# charge_drv.net
KiCad netlist of a schematic drawn in Altium Designer
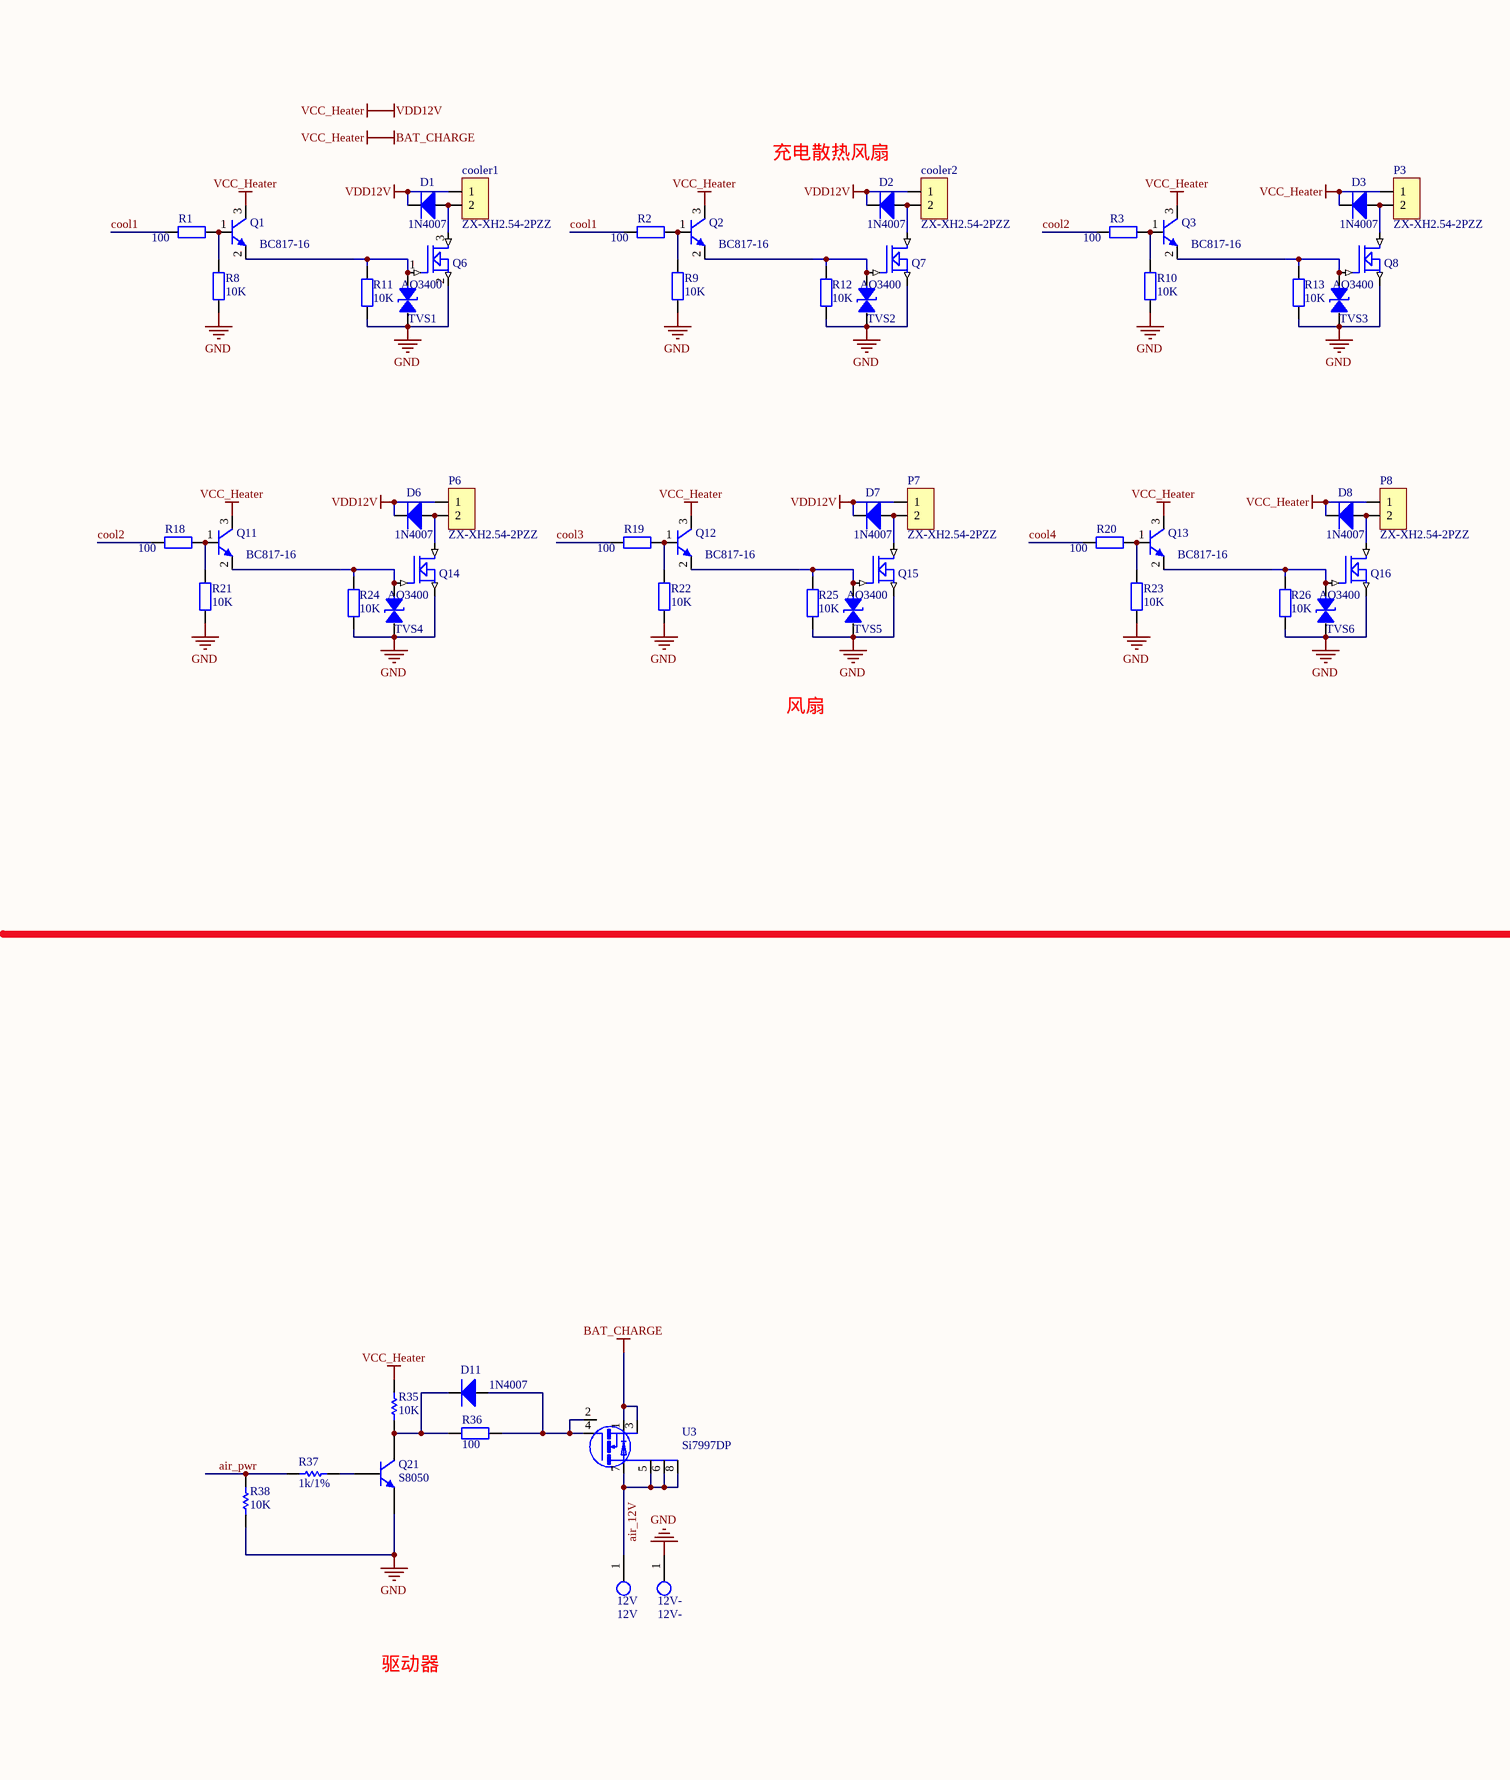
[diagram p0: charge_drv.SchDoc, left]
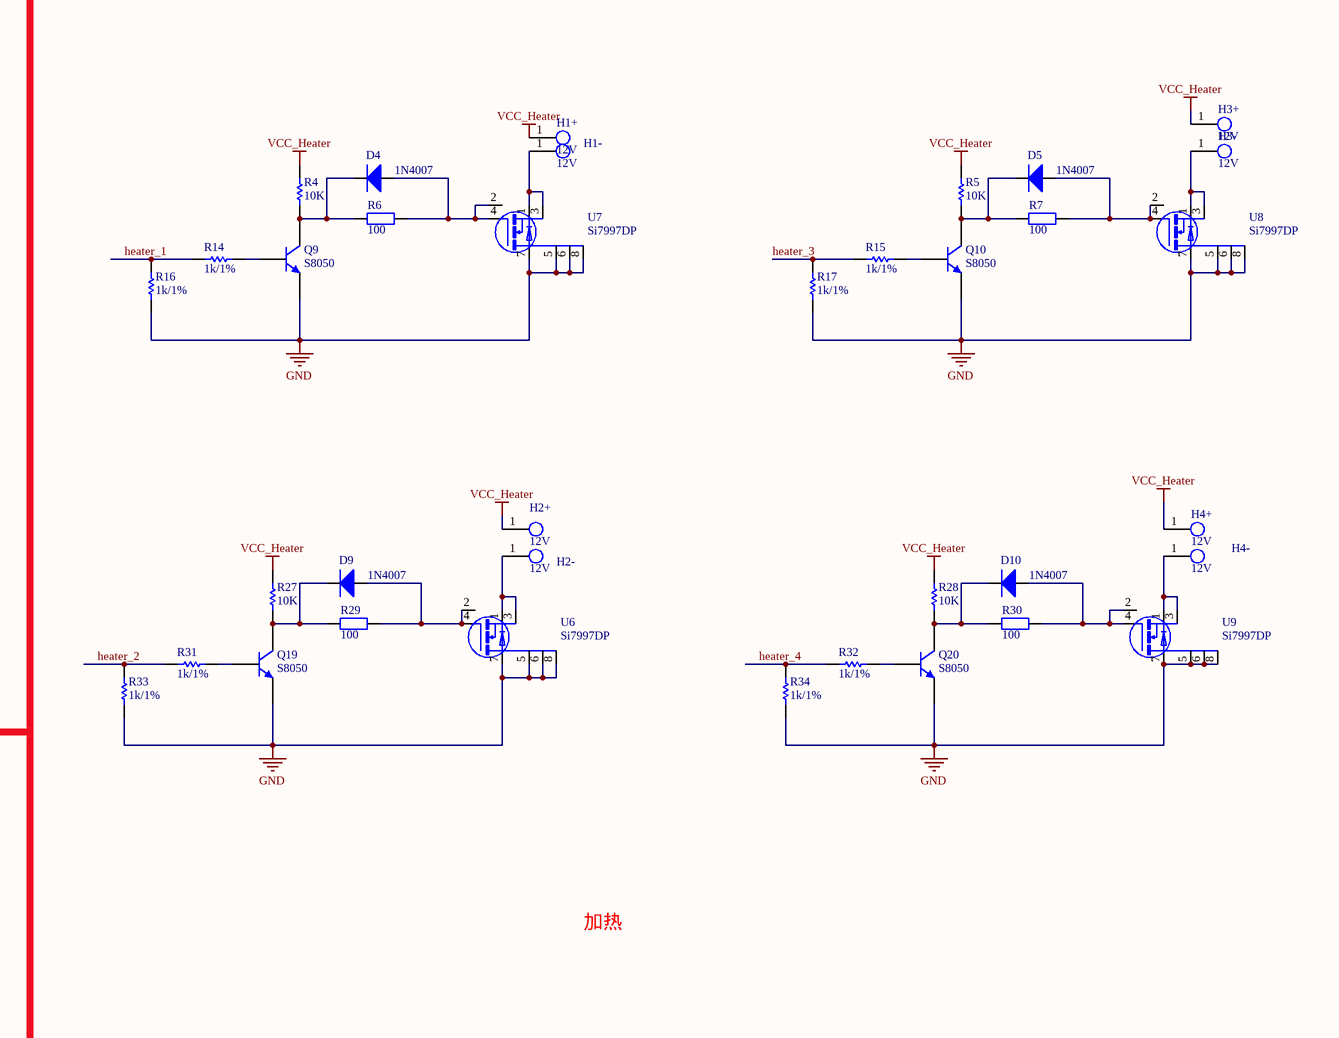
[diagram p1: charge_drv.SchDoc, right]

(export (version "E")
  (design (tool "Eeschema 10.0.6"))
  (components
    (comp (ref "12V") (value "12V") (footprint "FIX-4.5") (libsource (lib "Schlib_20110825") (part "TP")))
    (comp (ref "12V-") (value "12V-") (footprint "FIX-4.5") (libsource (lib "Schlib_20110825") (part "TP")))
    (comp (ref "cooler1")
      (value "ZX-XH2.54-2PZZ")
      (footprint "SIP-2A")
      (description "XH2.54 2P 立贴")
      (libsource (lib "XiaoyI") (part "SIP-2"))
    )
    (comp (ref "cooler2")
      (value "ZX-XH2.54-2PZZ")
      (footprint "SIP-2A")
      (description "XH2.54 2P 立贴")
      (libsource (lib "XiaoyI") (part "SIP-2"))
    )
    (comp (ref "D1")
      (value "1N4007")
      (footprint "DO-214-AC")
      (description "贴片二极管")
      (libsource (lib "XiaoyI") (part "DIODE2"))
    )
    (comp (ref "D2")
      (value "1N4007")
      (footprint "DO-214-AC")
      (description "贴片二极管")
      (libsource (lib "XiaoyI") (part "DIODE2"))
    )
    (comp (ref "D3")
      (value "1N4007")
      (footprint "DO-214-AC")
      (description "贴片二极管")
      (libsource (lib "XiaoyI") (part "DIODE2"))
    )
    (comp (ref "D4")
      (value "1N4007")
      (footprint "DO-214-AC")
      (description "贴片二极管")
      (libsource (lib "XiaoyI") (part "DIODE2"))
    )
    (comp (ref "D5")
      (value "1N4007")
      (footprint "DO-214-AC")
      (description "贴片二极管")
      (libsource (lib "XiaoyI") (part "DIODE2"))
    )
    (comp (ref "D6")
      (value "1N4007")
      (footprint "DO-214-AC")
      (description "贴片二极管")
      (libsource (lib "XiaoyI") (part "DIODE2"))
    )
    (comp (ref "D7")
      (value "1N4007")
      (footprint "DO-214-AC")
      (description "贴片二极管")
      (libsource (lib "XiaoyI") (part "DIODE2"))
    )
    (comp (ref "D8")
      (value "1N4007")
      (footprint "DO-214-AC")
      (description "贴片二极管")
      (libsource (lib "XiaoyI") (part "DIODE2"))
    )
    (comp (ref "D9")
      (value "1N4007")
      (footprint "DO-214-AC")
      (description "贴片二极管")
      (libsource (lib "XiaoyI") (part "DIODE2"))
    )
    (comp (ref "D10")
      (value "1N4007")
      (footprint "DO-214-AC")
      (description "贴片二极管")
      (libsource (lib "XiaoyI") (part "DIODE2"))
    )
    (comp (ref "D11")
      (value "1N4007")
      (footprint "DO-214-AC")
      (description "贴片二极管")
      (libsource (lib "XiaoyI") (part "DIODE2"))
    )
    (comp (ref "H1+") (value "12V") (footprint "FIX-4.5") (libsource (lib "Schlib_20110825") (part "TP")))
    (comp (ref "H1-") (value "12V") (footprint "FIX-4.5") (libsource (lib "Schlib_20110825") (part "TP")))
    (comp (ref "H2+") (value "12V") (footprint "FIX-4.5") (libsource (lib "Schlib_20110825") (part "TP")))
    (comp (ref "H2-") (value "12V") (footprint "FIX-4.5") (libsource (lib "Schlib_20110825") (part "TP")))
    (comp (ref "H3+") (value "12V") (footprint "FIX-4.5") (libsource (lib "Schlib_20110825") (part "TP")))
    (comp (ref "H3-") (value "12V") (footprint "FIX-4.5") (libsource (lib "Schlib_20110825") (part "TP")))
    (comp (ref "H4+") (value "12V") (footprint "FIX-4.5") (libsource (lib "Schlib_20110825") (part "TP")))
    (comp (ref "H4-") (value "12V") (footprint "FIX-4.5") (libsource (lib "Schlib_20110825") (part "TP")))
    (comp (ref "P3")
      (value "ZX-XH2.54-2PZZ")
      (footprint "SIP-2A")
      (description "XH2.54 2P 立贴")
      (libsource (lib "XiaoyI") (part "SIP-2"))
    )
    (comp (ref "P6")
      (value "ZX-XH2.54-2PZZ")
      (footprint "SIP-2A")
      (description "XH2.54 2P 立贴")
      (libsource (lib "XiaoyI") (part "SIP-2"))
    )
    (comp (ref "P7")
      (value "ZX-XH2.54-2PZZ")
      (footprint "SIP-2A")
      (description "XH2.54 2P 立贴")
      (libsource (lib "XiaoyI") (part "SIP-2"))
    )
    (comp (ref "P8")
      (value "ZX-XH2.54-2PZZ")
      (footprint "SIP-2A")
      (description "XH2.54 2P 立贴")
      (libsource (lib "XiaoyI") (part "SIP-2"))
    )
    (comp (ref "Q1")
      (value "BC817-16")
      (footprint "SOT23-3")
      (description "三极管")
      (libsource (lib "XiaoyI") (part "NPN-1"))
    )
    (comp (ref "Q2")
      (value "BC817-16")
      (footprint "SOT23-3")
      (description "三极管")
      (libsource (lib "XiaoyI") (part "NPN-1"))
    )
    (comp (ref "Q3")
      (value "BC817-16")
      (footprint "SOT23-3")
      (description "三极管")
      (libsource (lib "XiaoyI") (part "NPN-1"))
    )
    (comp (ref "Q6")
      (value "AO3400")
      (footprint "SOT23-3")
      (description "MOSFET N")
      (libsource (lib "") (part "MOSFET N_1"))
    )
    (comp (ref "Q7")
      (value "AO3400")
      (footprint "SOT23-3")
      (description "MOSFET N")
      (libsource (lib "XiaoyI") (part "MOSFET N"))
    )
    (comp (ref "Q8")
      (value "AO3400")
      (footprint "SOT23-3")
      (description "MOSFET N")
      (libsource (lib "XiaoyI") (part "MOSFET N"))
    )
    (comp (ref "Q9")
      (value "S8050")
      (footprint "SOT23-3")
      (description "NPN Bipolar Transistor")
      (fields (field (name "PUBLISHER") "Altium Limited"))
      (libsource (lib "Miscellaneous Devices") (part "NPN"))
    )
    (comp (ref "Q10")
      (value "S8050")
      (footprint "SOT23-3")
      (description "NPN Bipolar Transistor")
      (fields (field (name "PUBLISHER") "Altium Limited"))
      (libsource (lib "Miscellaneous Devices") (part "NPN"))
    )
    (comp (ref "Q11")
      (value "BC817-16")
      (footprint "SOT23-3")
      (description "三极管")
      (libsource (lib "XiaoyI") (part "NPN-1"))
    )
    (comp (ref "Q12")
      (value "BC817-16")
      (footprint "SOT23-3")
      (description "三极管")
      (libsource (lib "XiaoyI") (part "NPN-1"))
    )
    (comp (ref "Q13")
      (value "BC817-16")
      (footprint "SOT23-3")
      (description "三极管")
      (libsource (lib "XiaoyI") (part "NPN-1"))
    )
    (comp (ref "Q14")
      (value "AO3400")
      (footprint "SOT23-3")
      (description "MOSFET N")
      (libsource (lib "XiaoyI") (part "MOSFET N"))
    )
    (comp (ref "Q15")
      (value "AO3400")
      (footprint "SOT23-3")
      (description "MOSFET N")
      (libsource (lib "XiaoyI") (part "MOSFET N"))
    )
    (comp (ref "Q16")
      (value "AO3400")
      (footprint "SOT23-3")
      (description "MOSFET N")
      (libsource (lib "XiaoyI") (part "MOSFET N"))
    )
    (comp (ref "Q19")
      (value "S8050")
      (footprint "SOT23-3")
      (description "NPN Bipolar Transistor")
      (fields (field (name "PUBLISHER") "Altium Limited"))
      (libsource (lib "Miscellaneous Devices") (part "NPN"))
    )
    (comp (ref "Q20")
      (value "S8050")
      (footprint "SOT23-3")
      (description "NPN Bipolar Transistor")
      (fields (field (name "PUBLISHER") "Altium Limited"))
      (libsource (lib "Miscellaneous Devices") (part "NPN"))
    )
    (comp (ref "Q21")
      (value "S8050")
      (footprint "SOT23-3")
      (description "NPN Bipolar Transistor")
      (fields (field (name "PUBLISHER") "Altium Limited"))
      (libsource (lib "Miscellaneous Devices") (part "NPN"))
    )
    (comp (ref "R1")
      (value "100")
      (footprint "0603R")
      (description "贴片电阻 5%")
      (libsource (lib "XiaoyI") (part "RES-SOP"))
    )
    (comp (ref "R2")
      (value "100")
      (footprint "0603R")
      (description "贴片电阻 5%")
      (libsource (lib "XiaoyI") (part "RES-SOP"))
    )
    (comp (ref "R3")
      (value "100")
      (footprint "0603R")
      (description "贴片电阻 5%")
      (libsource (lib "XiaoyI") (part "RES-SOP"))
    )
    (comp (ref "R4")
      (value "10K")
      (footprint "0603R")
      (description "Resistor")
      (fields (field (name "PUBLISHER") "Altium Limited"))
      (libsource (lib "Miscellaneous Devices") (part "Res1"))
    )
    (comp (ref "R5")
      (value "10K")
      (footprint "0603R")
      (description "Resistor")
      (fields (field (name "PUBLISHER") "Altium Limited"))
      (libsource (lib "Miscellaneous Devices") (part "Res1"))
    )
    (comp (ref "R6")
      (value "100")
      (footprint "0603R")
      (description "贴片电阻 5%")
      (libsource (lib "") (part "RES-SOP_3"))
    )
    (comp (ref "R7")
      (value "100")
      (footprint "0603R")
      (description "贴片电阻 5%")
      (libsource (lib "") (part "RES-SOP_3"))
    )
    (comp (ref "R8")
      (value "10K")
      (footprint "0603R")
      (description "贴片电阻 5%")
      (libsource (lib "") (part "RES-SOP_2"))
    )
    (comp (ref "R9")
      (value "10K")
      (footprint "0603R")
      (description "贴片电阻 5%")
      (libsource (lib "") (part "RES-SOP_2"))
    )
    (comp (ref "R10")
      (value "10K")
      (footprint "0603R")
      (description "贴片电阻 5%")
      (libsource (lib "") (part "RES-SOP_2"))
    )
    (comp (ref "R11")
      (value "10K")
      (footprint "0603R")
      (description "贴片电阻 5%")
      (libsource (lib "") (part "RES-SOP_1"))
    )
    (comp (ref "R12")
      (value "10K")
      (footprint "0603R")
      (description "贴片电阻 5%")
      (libsource (lib "") (part "RES-SOP_1"))
    )
    (comp (ref "R13")
      (value "10K")
      (footprint "0603R")
      (description "贴片电阻 5%")
      (libsource (lib "") (part "RES-SOP_1"))
    )
    (comp (ref "R14")
      (value "1k/1%")
      (footprint "0603R")
      (description "Resistor")
      (fields (field (name "PUBLISHER") "Altium Limited"))
      (libsource (lib "Miscellaneous Devices") (part "Res1"))
    )
    (comp (ref "R15")
      (value "1k/1%")
      (footprint "0603R")
      (description "Resistor")
      (fields (field (name "PUBLISHER") "Altium Limited"))
      (libsource (lib "Miscellaneous Devices") (part "Res1"))
    )
    (comp (ref "R16")
      (value "1k/1%")
      (footprint "0603R")
      (description "Resistor")
      (fields (field (name "PUBLISHER") "Altium Limited"))
      (libsource (lib "Miscellaneous Devices") (part "Res1"))
    )
    (comp (ref "R17")
      (value "1k/1%")
      (footprint "0603R")
      (description "Resistor")
      (fields (field (name "PUBLISHER") "Altium Limited"))
      (libsource (lib "Miscellaneous Devices") (part "Res1"))
    )
    (comp (ref "R18")
      (value "100")
      (footprint "0603R")
      (description "贴片电阻 5%")
      (libsource (lib "XiaoyI") (part "RES-SOP"))
    )
    (comp (ref "R19")
      (value "100")
      (footprint "0603R")
      (description "贴片电阻 5%")
      (libsource (lib "XiaoyI") (part "RES-SOP"))
    )
    (comp (ref "R20")
      (value "100")
      (footprint "0603R")
      (description "贴片电阻 5%")
      (libsource (lib "XiaoyI") (part "RES-SOP"))
    )
    (comp (ref "R21")
      (value "10K")
      (footprint "0603R")
      (description "贴片电阻 5%")
      (libsource (lib "") (part "RES-SOP_2"))
    )
    (comp (ref "R22")
      (value "10K")
      (footprint "0603R")
      (description "贴片电阻 5%")
      (libsource (lib "") (part "RES-SOP_2"))
    )
    (comp (ref "R23")
      (value "10K")
      (footprint "0603R")
      (description "贴片电阻 5%")
      (libsource (lib "") (part "RES-SOP_2"))
    )
    (comp (ref "R24")
      (value "10K")
      (footprint "0603R")
      (description "贴片电阻 5%")
      (libsource (lib "") (part "RES-SOP_1"))
    )
    (comp (ref "R25")
      (value "10K")
      (footprint "0603R")
      (description "贴片电阻 5%")
      (libsource (lib "") (part "RES-SOP_1"))
    )
    (comp (ref "R26")
      (value "10K")
      (footprint "0603R")
      (description "贴片电阻 5%")
      (libsource (lib "") (part "RES-SOP_1"))
    )
    (comp (ref "R27")
      (value "10K")
      (footprint "0603R")
      (description "Resistor")
      (fields (field (name "PUBLISHER") "Altium Limited"))
      (libsource (lib "Miscellaneous Devices") (part "Res1"))
    )
    (comp (ref "R28")
      (value "10K")
      (footprint "0603R")
      (description "Resistor")
      (fields (field (name "PUBLISHER") "Altium Limited"))
      (libsource (lib "Miscellaneous Devices") (part "Res1"))
    )
    (comp (ref "R29")
      (value "100")
      (footprint "0603R")
      (description "贴片电阻 5%")
      (libsource (lib "") (part "RES-SOP_3"))
    )
    (comp (ref "R30")
      (value "100")
      (footprint "0603R")
      (description "贴片电阻 5%")
      (libsource (lib "") (part "RES-SOP_3"))
    )
    (comp (ref "R31")
      (value "1k/1%")
      (footprint "0603R")
      (description "Resistor")
      (fields (field (name "PUBLISHER") "Altium Limited"))
      (libsource (lib "Miscellaneous Devices") (part "Res1"))
    )
    (comp (ref "R32")
      (value "1k/1%")
      (footprint "0603R")
      (description "Resistor")
      (fields (field (name "PUBLISHER") "Altium Limited"))
      (libsource (lib "Miscellaneous Devices") (part "Res1"))
    )
    (comp (ref "R33")
      (value "1k/1%")
      (footprint "0603R")
      (description "Resistor")
      (fields (field (name "PUBLISHER") "Altium Limited"))
      (libsource (lib "Miscellaneous Devices") (part "Res1"))
    )
    (comp (ref "R34")
      (value "1k/1%")
      (footprint "0603R")
      (description "Resistor")
      (fields (field (name "PUBLISHER") "Altium Limited"))
      (libsource (lib "Miscellaneous Devices") (part "Res1"))
    )
    (comp (ref "R35")
      (value "10K")
      (footprint "0603R")
      (description "Resistor")
      (fields (field (name "PUBLISHER") "Altium Limited"))
      (libsource (lib "Miscellaneous Devices") (part "Res1"))
    )
    (comp (ref "R36")
      (value "100")
      (footprint "0603R")
      (description "贴片电阻 5%")
      (libsource (lib "") (part "RES-SOP_3"))
    )
    (comp (ref "R37")
      (value "1k/1%")
      (footprint "0603R")
      (description "Resistor")
      (fields (field (name "PUBLISHER") "Altium Limited"))
      (libsource (lib "Miscellaneous Devices") (part "Res1"))
    )
    (comp (ref "R38")
      (value "10K")
      (footprint "0603R")
      (description "Resistor")
      (fields (field (name "PUBLISHER") "Altium Limited"))
      (libsource (lib "Miscellaneous Devices") (part "Res1"))
    )
    (comp (ref "TVS1")
      (value "ESD5Z5.0CT1G")
      (footprint "SOD-523")
      (description "TVS")
      (libsource (lib "XiaoyI") (part "TVS-1"))
    )
    (comp (ref "TVS2")
      (value "ESD5Z5.0CT1G")
      (footprint "SOD-523")
      (description "TVS")
      (libsource (lib "XiaoyI") (part "TVS-1"))
    )
    (comp (ref "TVS3")
      (value "ESD5Z5.0CT1G")
      (footprint "SOD-523")
      (description "TVS")
      (libsource (lib "XiaoyI") (part "TVS-1"))
    )
    (comp (ref "TVS4")
      (value "ESD5Z5.0CT1G")
      (footprint "SOD-523")
      (description "TVS")
      (libsource (lib "XiaoyI") (part "TVS-1"))
    )
    (comp (ref "TVS5")
      (value "ESD5Z5.0CT1G")
      (footprint "SOD-523")
      (description "TVS")
      (libsource (lib "XiaoyI") (part "TVS-1"))
    )
    (comp (ref "TVS6")
      (value "ESD5Z5.0CT1G")
      (footprint "SOD-523")
      (description "TVS")
      (libsource (lib "XiaoyI") (part "TVS-1"))
    )
    (comp (ref "U3")
      (value "Si7997DP")
      (footprint "PowerPAK SO-8")
      (description "Sia430DJ")
      (libsource (lib "Schlib_20110825") (part "Si7997DP"))
    )
    (comp (ref "U6")
      (value "Si7997DP")
      (footprint "PowerPAK SO-8")
      (description "Sia430DJ")
      (libsource (lib "Schlib_20110825") (part "Si7997DP"))
    )
    (comp (ref "U7")
      (value "Si7997DP")
      (footprint "PowerPAK SO-8")
      (description "Sia430DJ")
      (libsource (lib "Schlib_20110825") (part "Si7997DP"))
    )
    (comp (ref "U8")
      (value "Si7997DP")
      (footprint "PowerPAK SO-8")
      (description "Sia430DJ")
      (libsource (lib "Schlib_20110825") (part "Si7997DP"))
    )
    (comp (ref "U9")
      (value "Si7997DP")
      (footprint "PowerPAK SO-8")
      (description "Sia430DJ")
      (libsource (lib "Schlib_20110825") (part "Si7997DP"))
    )
  )
  (nets
    (net (code "1") (name "/air_12V") (class "Default")
      (node (ref "12V") (pin "1") (pintype "passive"))
      (node (ref "U3") (pin "5") (pinfunction "D_5") (pintype "passive"))
      (node (ref "U3") (pin "6") (pinfunction "D_6") (pintype "passive"))
      (node (ref "U3") (pin "7") (pinfunction "D_7") (pintype "passive"))
      (node (ref "U3") (pin "8") (pinfunction "D_8") (pintype "passive"))
    )
    (net (code "2") (name "/air_pwr") (class "Default")
      (node (ref "R37") (pin "2") (pinfunction "2_2") (pintype "passive"))
      (node (ref "R38") (pin "1") (pinfunction "1_1") (pintype "passive"))
    )
    (net (code "3") (name "/cool1") (class "Default")
      (node (ref "R1") (pin "2") (pinfunction "2_2") (pintype "passive"))
      (node (ref "R2") (pin "2") (pinfunction "2_2") (pintype "passive"))
    )
    (net (code "4") (name "/cool2") (class "Default")
      (node (ref "R18") (pin "2") (pinfunction "2_2") (pintype "passive"))
      (node (ref "R3") (pin "2") (pinfunction "2_2") (pintype "passive"))
    )
    (net (code "5") (name "/cool3") (class "Default")
      (node (ref "R19") (pin "2") (pinfunction "2_2") (pintype "passive"))
    )
    (net (code "6") (name "/cool4") (class "Default")
      (node (ref "R20") (pin "2") (pinfunction "2_2") (pintype "passive"))
    )
    (net (code "7") (name "/heater_1") (class "Default")
      (node (ref "R14") (pin "2") (pinfunction "2_2") (pintype "passive"))
      (node (ref "R16") (pin "1") (pinfunction "1_1") (pintype "passive"))
    )
    (net (code "8") (name "/heater_2") (class "Default")
      (node (ref "R31") (pin "2") (pinfunction "2_2") (pintype "passive"))
      (node (ref "R33") (pin "1") (pinfunction "1_1") (pintype "passive"))
    )
    (net (code "9") (name "/heater_3") (class "Default")
      (node (ref "R15") (pin "2") (pinfunction "2_2") (pintype "passive"))
      (node (ref "R17") (pin "1") (pinfunction "1_1") (pintype "passive"))
    )
    (net (code "10") (name "/heater_4") (class "Default")
      (node (ref "R32") (pin "2") (pinfunction "2_2") (pintype "passive"))
      (node (ref "R34") (pin "1") (pinfunction "1_1") (pintype "passive"))
    )
    (net (code "11") (name "BAT_CHARGE") (class "Default")
      (node (ref "D1") (pin "2") (pinfunction "K_2") (pintype "passive"))
      (node (ref "D2") (pin "2") (pinfunction "K_2") (pintype "passive"))
      (node (ref "D3") (pin "2") (pinfunction "K_2") (pintype "passive"))
      (node (ref "D6") (pin "2") (pinfunction "K_2") (pintype "passive"))
      (node (ref "D7") (pin "2") (pinfunction "K_2") (pintype "passive"))
      (node (ref "D8") (pin "2") (pinfunction "K_2") (pintype "passive"))
      (node (ref "H1+") (pin "1") (pintype "passive"))
      (node (ref "H2+") (pin "1") (pintype "passive"))
      (node (ref "H3+") (pin "1") (pintype "passive"))
      (node (ref "H4+") (pin "1") (pintype "passive"))
      (node (ref "P3") (pin "1") (pinfunction "1_1") (pintype "passive"))
      (node (ref "P6") (pin "1") (pinfunction "1_1") (pintype "passive"))
      (node (ref "P7") (pin "1") (pinfunction "1_1") (pintype "passive"))
      (node (ref "P8") (pin "1") (pinfunction "1_1") (pintype "passive"))
      (node (ref "Q1") (pin "3") (pinfunction "C_3") (pintype "passive"))
      (node (ref "Q11") (pin "3") (pinfunction "C_3") (pintype "passive"))
      (node (ref "Q12") (pin "3") (pinfunction "C_3") (pintype "passive"))
      (node (ref "Q13") (pin "3") (pinfunction "C_3") (pintype "passive"))
      (node (ref "Q2") (pin "3") (pinfunction "C_3") (pintype "passive"))
      (node (ref "Q3") (pin "3") (pinfunction "C_3") (pintype "passive"))
      (node (ref "R27") (pin "2") (pinfunction "2_2") (pintype "passive"))
      (node (ref "R28") (pin "2") (pinfunction "2_2") (pintype "passive"))
      (node (ref "R35") (pin "2") (pinfunction "2_2") (pintype "passive"))
      (node (ref "R4") (pin "2") (pinfunction "2_2") (pintype "passive"))
      (node (ref "R5") (pin "2") (pinfunction "2_2") (pintype "passive"))
      (node (ref "U3") (pin "1") (pinfunction "S_1") (pintype "passive"))
      (node (ref "U3") (pin "3") (pinfunction "S_3") (pintype "passive"))
      (node (ref "cooler1") (pin "1") (pinfunction "1_1") (pintype "passive"))
      (node (ref "cooler2") (pin "1") (pinfunction "1_1") (pintype "passive"))
    )
    (net (code "12") (name "GND") (class "Default")
      (node (ref "12V-") (pin "1") (pintype "passive"))
      (node (ref "Q10") (pin "2") (pinfunction "E_2") (pintype "passive"))
      (node (ref "Q14") (pin "2") (pinfunction "S_2") (pintype "output"))
      (node (ref "Q15") (pin "2") (pinfunction "S_2") (pintype "output"))
      (node (ref "Q16") (pin "2") (pinfunction "S_2") (pintype "output"))
      (node (ref "Q19") (pin "2") (pinfunction "E_2") (pintype "passive"))
      (node (ref "Q20") (pin "2") (pinfunction "E_2") (pintype "passive"))
      (node (ref "Q21") (pin "2") (pinfunction "E_2") (pintype "passive"))
      (node (ref "Q6") (pin "2") (pinfunction "S_2") (pintype "output"))
      (node (ref "Q7") (pin "2") (pinfunction "S_2") (pintype "output"))
      (node (ref "Q8") (pin "2") (pinfunction "S_2") (pintype "output"))
      (node (ref "Q9") (pin "2") (pinfunction "E_2") (pintype "passive"))
      (node (ref "R10") (pin "1") (pinfunction "1_1") (pintype "passive"))
      (node (ref "R11") (pin "2") (pinfunction "2_2") (pintype "passive"))
      (node (ref "R12") (pin "2") (pinfunction "2_2") (pintype "passive"))
      (node (ref "R13") (pin "2") (pinfunction "2_2") (pintype "passive"))
      (node (ref "R16") (pin "2") (pinfunction "2_2") (pintype "passive"))
      (node (ref "R17") (pin "2") (pinfunction "2_2") (pintype "passive"))
      (node (ref "R21") (pin "1") (pinfunction "1_1") (pintype "passive"))
      (node (ref "R22") (pin "1") (pinfunction "1_1") (pintype "passive"))
      (node (ref "R23") (pin "1") (pinfunction "1_1") (pintype "passive"))
      (node (ref "R24") (pin "2") (pinfunction "2_2") (pintype "passive"))
      (node (ref "R25") (pin "2") (pinfunction "2_2") (pintype "passive"))
      (node (ref "R26") (pin "2") (pinfunction "2_2") (pintype "passive"))
      (node (ref "R33") (pin "2") (pinfunction "2_2") (pintype "passive"))
      (node (ref "R34") (pin "2") (pinfunction "2_2") (pintype "passive"))
      (node (ref "R38") (pin "2") (pinfunction "2_2") (pintype "passive"))
      (node (ref "R8") (pin "1") (pinfunction "1_1") (pintype "passive"))
      (node (ref "R9") (pin "1") (pinfunction "1_1") (pintype "passive"))
      (node (ref "TVS1") (pin "1") (pinfunction "A_1") (pintype "passive"))
      (node (ref "TVS2") (pin "1") (pinfunction "A_1") (pintype "passive"))
      (node (ref "TVS3") (pin "1") (pinfunction "A_1") (pintype "passive"))
      (node (ref "TVS4") (pin "1") (pinfunction "A_1") (pintype "passive"))
      (node (ref "TVS5") (pin "1") (pinfunction "A_1") (pintype "passive"))
      (node (ref "TVS6") (pin "1") (pinfunction "A_1") (pintype "passive"))
      (node (ref "U6") (pin "5") (pinfunction "D_5") (pintype "passive"))
      (node (ref "U6") (pin "6") (pinfunction "D_6") (pintype "passive"))
      (node (ref "U6") (pin "7") (pinfunction "D_7") (pintype "passive"))
      (node (ref "U6") (pin "8") (pinfunction "D_8") (pintype "passive"))
      (node (ref "U7") (pin "5") (pinfunction "D_5") (pintype "passive"))
      (node (ref "U7") (pin "6") (pinfunction "D_6") (pintype "passive"))
      (node (ref "U7") (pin "7") (pinfunction "D_7") (pintype "passive"))
      (node (ref "U7") (pin "8") (pinfunction "D_8") (pintype "passive"))
      (node (ref "U8") (pin "5") (pinfunction "D_5") (pintype "passive"))
      (node (ref "U8") (pin "6") (pinfunction "D_6") (pintype "passive"))
      (node (ref "U8") (pin "7") (pinfunction "D_7") (pintype "passive"))
      (node (ref "U8") (pin "8") (pinfunction "D_8") (pintype "passive"))
      (node (ref "U9") (pin "5") (pinfunction "D_5") (pintype "passive"))
      (node (ref "U9") (pin "6") (pinfunction "D_6") (pintype "passive"))
      (node (ref "U9") (pin "7") (pinfunction "D_7") (pintype "passive"))
      (node (ref "U9") (pin "8") (pinfunction "D_8") (pintype "passive"))
    )
    (net (code "13") (name "Net-(D1-A)") (class "Default")
      (node (ref "D1") (pin "1") (pinfunction "A_1") (pintype "passive"))
      (node (ref "Q6") (pin "3") (pinfunction "D_3") (pintype "input"))
      (node (ref "cooler1") (pin "2") (pinfunction "2_2") (pintype "passive"))
    )
    (net (code "14") (name "Net-(D2-A)") (class "Default")
      (node (ref "D2") (pin "1") (pinfunction "A_1") (pintype "passive"))
      (node (ref "Q7") (pin "3") (pinfunction "D_3") (pintype "input"))
      (node (ref "cooler2") (pin "2") (pinfunction "2_2") (pintype "passive"))
    )
    (net (code "15") (name "Net-(D3-A)") (class "Default")
      (node (ref "D3") (pin "1") (pinfunction "A_1") (pintype "passive"))
      (node (ref "P3") (pin "2") (pinfunction "2_2") (pintype "passive"))
      (node (ref "Q8") (pin "3") (pinfunction "D_3") (pintype "input"))
    )
    (net (code "16") (name "Net-(D4-A)") (class "Default")
      (node (ref "D4") (pin "1") (pinfunction "A_1") (pintype "passive"))
      (node (ref "R6") (pin "2") (pinfunction "2_2") (pintype "passive"))
      (node (ref "U7") (pin "2") (pinfunction "G_2") (pintype "passive"))
      (node (ref "U7") (pin "4") (pinfunction "G_4") (pintype "passive"))
    )
    (net (code "17") (name "Net-(D4-K)") (class "Default")
      (node (ref "D4") (pin "2") (pinfunction "K_2") (pintype "passive"))
      (node (ref "Q9") (pin "3") (pinfunction "C_3") (pintype "passive"))
      (node (ref "R4") (pin "1") (pinfunction "1_1") (pintype "passive"))
      (node (ref "R6") (pin "1") (pinfunction "1_1") (pintype "passive"))
    )
    (net (code "18") (name "Net-(D5-A)") (class "Default")
      (node (ref "D5") (pin "1") (pinfunction "A_1") (pintype "passive"))
      (node (ref "R7") (pin "2") (pinfunction "2_2") (pintype "passive"))
      (node (ref "U8") (pin "2") (pinfunction "G_2") (pintype "passive"))
      (node (ref "U8") (pin "4") (pinfunction "G_4") (pintype "passive"))
    )
    (net (code "19") (name "Net-(D5-K)") (class "Default")
      (node (ref "D5") (pin "2") (pinfunction "K_2") (pintype "passive"))
      (node (ref "Q10") (pin "3") (pinfunction "C_3") (pintype "passive"))
      (node (ref "R5") (pin "1") (pinfunction "1_1") (pintype "passive"))
      (node (ref "R7") (pin "1") (pinfunction "1_1") (pintype "passive"))
    )
    (net (code "20") (name "Net-(D6-A)") (class "Default")
      (node (ref "D6") (pin "1") (pinfunction "A_1") (pintype "passive"))
      (node (ref "P6") (pin "2") (pinfunction "2_2") (pintype "passive"))
      (node (ref "Q14") (pin "3") (pinfunction "D_3") (pintype "input"))
    )
    (net (code "21") (name "Net-(D7-A)") (class "Default")
      (node (ref "D7") (pin "1") (pinfunction "A_1") (pintype "passive"))
      (node (ref "P7") (pin "2") (pinfunction "2_2") (pintype "passive"))
      (node (ref "Q15") (pin "3") (pinfunction "D_3") (pintype "input"))
    )
    (net (code "22") (name "Net-(D8-A)") (class "Default")
      (node (ref "D8") (pin "1") (pinfunction "A_1") (pintype "passive"))
      (node (ref "P8") (pin "2") (pinfunction "2_2") (pintype "passive"))
      (node (ref "Q16") (pin "3") (pinfunction "D_3") (pintype "input"))
    )
    (net (code "23") (name "Net-(D9-A)") (class "Default")
      (node (ref "D9") (pin "1") (pinfunction "A_1") (pintype "passive"))
      (node (ref "R29") (pin "2") (pinfunction "2_2") (pintype "passive"))
      (node (ref "U6") (pin "2") (pinfunction "G_2") (pintype "passive"))
      (node (ref "U6") (pin "4") (pinfunction "G_4") (pintype "passive"))
    )
    (net (code "24") (name "Net-(D9-K)") (class "Default")
      (node (ref "D9") (pin "2") (pinfunction "K_2") (pintype "passive"))
      (node (ref "Q19") (pin "3") (pinfunction "C_3") (pintype "passive"))
      (node (ref "R27") (pin "1") (pinfunction "1_1") (pintype "passive"))
      (node (ref "R29") (pin "1") (pinfunction "1_1") (pintype "passive"))
    )
    (net (code "25") (name "Net-(D10-A)") (class "Default")
      (node (ref "D10") (pin "1") (pinfunction "A_1") (pintype "passive"))
      (node (ref "R30") (pin "2") (pinfunction "2_2") (pintype "passive"))
      (node (ref "U9") (pin "2") (pinfunction "G_2") (pintype "passive"))
      (node (ref "U9") (pin "4") (pinfunction "G_4") (pintype "passive"))
    )
    (net (code "26") (name "Net-(D10-K)") (class "Default")
      (node (ref "D10") (pin "2") (pinfunction "K_2") (pintype "passive"))
      (node (ref "Q20") (pin "3") (pinfunction "C_3") (pintype "passive"))
      (node (ref "R28") (pin "1") (pinfunction "1_1") (pintype "passive"))
      (node (ref "R30") (pin "1") (pinfunction "1_1") (pintype "passive"))
    )
    (net (code "27") (name "Net-(D11-A)") (class "Default")
      (node (ref "D11") (pin "1") (pinfunction "A_1") (pintype "passive"))
      (node (ref "R36") (pin "2") (pinfunction "2_2") (pintype "passive"))
      (node (ref "U3") (pin "2") (pinfunction "G_2") (pintype "passive"))
      (node (ref "U3") (pin "4") (pinfunction "G_4") (pintype "passive"))
    )
    (net (code "28") (name "Net-(D11-K)") (class "Default")
      (node (ref "D11") (pin "2") (pinfunction "K_2") (pintype "passive"))
      (node (ref "Q21") (pin "3") (pinfunction "C_3") (pintype "passive"))
      (node (ref "R35") (pin "1") (pinfunction "1_1") (pintype "passive"))
      (node (ref "R36") (pin "1") (pinfunction "1_1") (pintype "passive"))
    )
    (net (code "29") (name "Net-(H1--Pad1)") (class "Default")
      (node (ref "H1-") (pin "1") (pintype "passive"))
      (node (ref "U7") (pin "1") (pinfunction "S_1") (pintype "passive"))
      (node (ref "U7") (pin "3") (pinfunction "S_3") (pintype "passive"))
    )
    (net (code "30") (name "Net-(H2--Pad1)") (class "Default")
      (node (ref "H2-") (pin "1") (pintype "passive"))
      (node (ref "U6") (pin "1") (pinfunction "S_1") (pintype "passive"))
      (node (ref "U6") (pin "3") (pinfunction "S_3") (pintype "passive"))
    )
    (net (code "31") (name "Net-(H3--Pad1)") (class "Default")
      (node (ref "H3-") (pin "1") (pintype "passive"))
      (node (ref "U8") (pin "1") (pinfunction "S_1") (pintype "passive"))
      (node (ref "U8") (pin "3") (pinfunction "S_3") (pintype "passive"))
    )
    (net (code "32") (name "Net-(H4--Pad1)") (class "Default")
      (node (ref "H4-") (pin "1") (pintype "passive"))
      (node (ref "U9") (pin "1") (pinfunction "S_1") (pintype "passive"))
      (node (ref "U9") (pin "3") (pinfunction "S_3") (pintype "passive"))
    )
    (net (code "33") (name "Net-(Q1-B)") (class "Default")
      (node (ref "Q1") (pin "1") (pinfunction "B_1") (pintype "passive"))
      (node (ref "R1") (pin "1") (pinfunction "1_1") (pintype "passive"))
      (node (ref "R8") (pin "2") (pinfunction "2_2") (pintype "passive"))
    )
    (net (code "34") (name "Net-(Q1-E)") (class "Default")
      (node (ref "Q1") (pin "2") (pinfunction "E_2") (pintype "passive"))
      (node (ref "Q6") (pin "1") (pinfunction "G_1") (pintype "input"))
      (node (ref "R11") (pin "1") (pinfunction "1_1") (pintype "passive"))
      (node (ref "TVS1") (pin "2") (pinfunction "B_2") (pintype "passive"))
    )
    (net (code "35") (name "Net-(Q2-B)") (class "Default")
      (node (ref "Q2") (pin "1") (pinfunction "B_1") (pintype "passive"))
      (node (ref "R2") (pin "1") (pinfunction "1_1") (pintype "passive"))
      (node (ref "R9") (pin "2") (pinfunction "2_2") (pintype "passive"))
    )
    (net (code "36") (name "Net-(Q2-E)") (class "Default")
      (node (ref "Q2") (pin "2") (pinfunction "E_2") (pintype "passive"))
      (node (ref "Q7") (pin "1") (pinfunction "G_1") (pintype "input"))
      (node (ref "R12") (pin "1") (pinfunction "1_1") (pintype "passive"))
      (node (ref "TVS2") (pin "2") (pinfunction "B_2") (pintype "passive"))
    )
    (net (code "37") (name "Net-(Q3-B)") (class "Default")
      (node (ref "Q3") (pin "1") (pinfunction "B_1") (pintype "passive"))
      (node (ref "R10") (pin "2") (pinfunction "2_2") (pintype "passive"))
      (node (ref "R3") (pin "1") (pinfunction "1_1") (pintype "passive"))
    )
    (net (code "38") (name "Net-(Q3-E)") (class "Default")
      (node (ref "Q3") (pin "2") (pinfunction "E_2") (pintype "passive"))
      (node (ref "Q8") (pin "1") (pinfunction "G_1") (pintype "input"))
      (node (ref "R13") (pin "1") (pinfunction "1_1") (pintype "passive"))
      (node (ref "TVS3") (pin "2") (pinfunction "B_2") (pintype "passive"))
    )
    (net (code "39") (name "Net-(Q9-B)") (class "Default")
      (node (ref "Q9") (pin "1") (pinfunction "B_1") (pintype "passive"))
      (node (ref "R14") (pin "1") (pinfunction "1_1") (pintype "passive"))
    )
    (net (code "40") (name "Net-(Q10-B)") (class "Default")
      (node (ref "Q10") (pin "1") (pinfunction "B_1") (pintype "passive"))
      (node (ref "R15") (pin "1") (pinfunction "1_1") (pintype "passive"))
    )
    (net (code "41") (name "Net-(Q11-B)") (class "Default")
      (node (ref "Q11") (pin "1") (pinfunction "B_1") (pintype "passive"))
      (node (ref "R18") (pin "1") (pinfunction "1_1") (pintype "passive"))
      (node (ref "R21") (pin "2") (pinfunction "2_2") (pintype "passive"))
    )
    (net (code "42") (name "Net-(Q11-E)") (class "Default")
      (node (ref "Q11") (pin "2") (pinfunction "E_2") (pintype "passive"))
      (node (ref "Q14") (pin "1") (pinfunction "G_1") (pintype "input"))
      (node (ref "R24") (pin "1") (pinfunction "1_1") (pintype "passive"))
      (node (ref "TVS4") (pin "2") (pinfunction "B_2") (pintype "passive"))
    )
    (net (code "43") (name "Net-(Q12-B)") (class "Default")
      (node (ref "Q12") (pin "1") (pinfunction "B_1") (pintype "passive"))
      (node (ref "R19") (pin "1") (pinfunction "1_1") (pintype "passive"))
      (node (ref "R22") (pin "2") (pinfunction "2_2") (pintype "passive"))
    )
    (net (code "44") (name "Net-(Q12-E)") (class "Default")
      (node (ref "Q12") (pin "2") (pinfunction "E_2") (pintype "passive"))
      (node (ref "Q15") (pin "1") (pinfunction "G_1") (pintype "input"))
      (node (ref "R25") (pin "1") (pinfunction "1_1") (pintype "passive"))
      (node (ref "TVS5") (pin "2") (pinfunction "B_2") (pintype "passive"))
    )
    (net (code "45") (name "Net-(Q13-B)") (class "Default")
      (node (ref "Q13") (pin "1") (pinfunction "B_1") (pintype "passive"))
      (node (ref "R20") (pin "1") (pinfunction "1_1") (pintype "passive"))
      (node (ref "R23") (pin "2") (pinfunction "2_2") (pintype "passive"))
    )
    (net (code "46") (name "Net-(Q13-E)") (class "Default")
      (node (ref "Q13") (pin "2") (pinfunction "E_2") (pintype "passive"))
      (node (ref "Q16") (pin "1") (pinfunction "G_1") (pintype "input"))
      (node (ref "R26") (pin "1") (pinfunction "1_1") (pintype "passive"))
      (node (ref "TVS6") (pin "2") (pinfunction "B_2") (pintype "passive"))
    )
    (net (code "47") (name "Net-(Q19-B)") (class "Default")
      (node (ref "Q19") (pin "1") (pinfunction "B_1") (pintype "passive"))
      (node (ref "R31") (pin "1") (pinfunction "1_1") (pintype "passive"))
    )
    (net (code "48") (name "Net-(Q20-B)") (class "Default")
      (node (ref "Q20") (pin "1") (pinfunction "B_1") (pintype "passive"))
      (node (ref "R32") (pin "1") (pinfunction "1_1") (pintype "passive"))
    )
    (net (code "49") (name "Net-(Q21-B)") (class "Default")
      (node (ref "Q21") (pin "1") (pinfunction "B_1") (pintype "passive"))
      (node (ref "R37") (pin "1") (pinfunction "1_1") (pintype "passive"))
    )
  )
)
